# PL_IO.net
KiCad netlist of a schematic drawn in Altium Designer
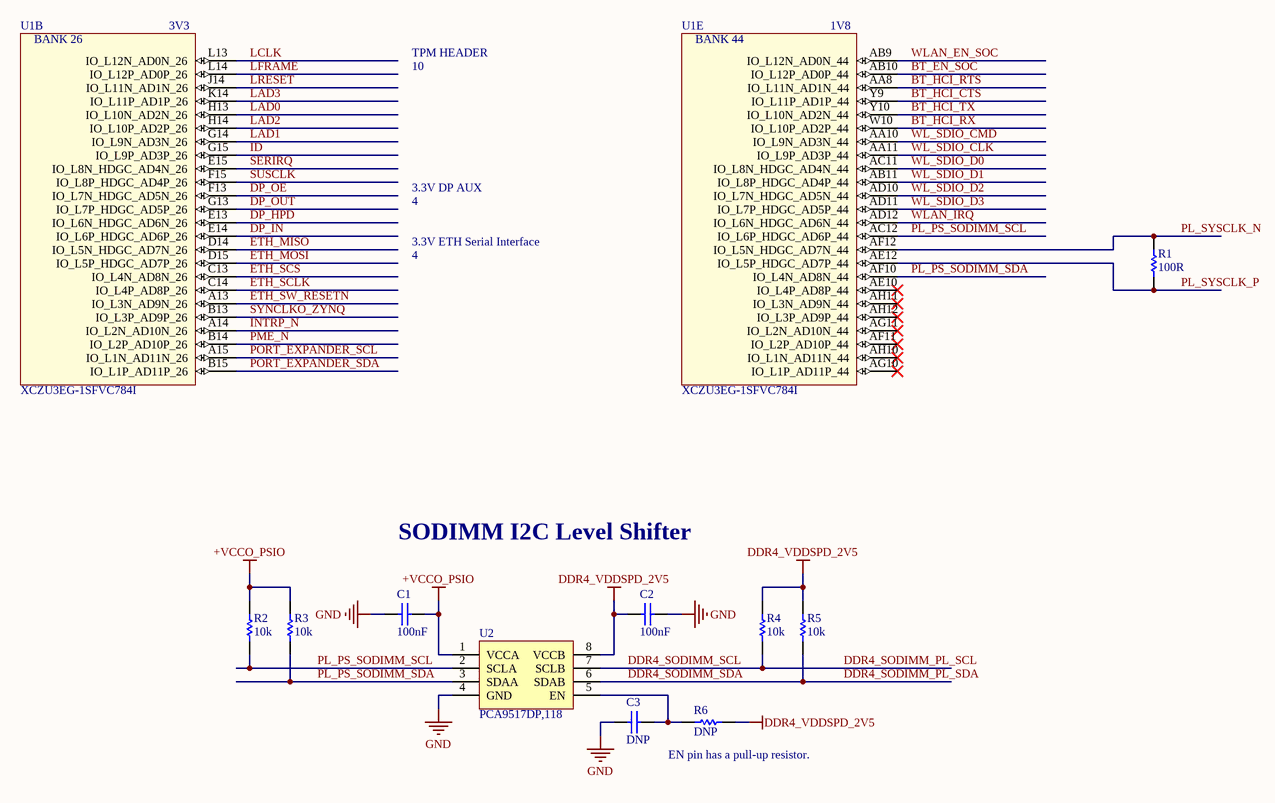
[diagram p0: PL_IO.SchDoc]

(export (version "E")
  (design (tool "Eeschema 10.0.6"))
  (components
    (comp (ref "C1")
      (value "100nF")
      (footprint "CAPC1005L_0402")
      (description "CAP CER 0.1UF 25V X7R 0402")
      (fields (field (name "VOLTAGE") "25V") (field (name "TOLERANCE") "10%"))
      (libsource (lib "Ultrascale_SchLib") (part "CAPCER0402X7R100N25V_10T"))
    )
    (comp (ref "C2")
      (value "100nF")
      (footprint "CAPC1005L_0402")
      (description "CAP CER 0.1UF 25V X7R 0402")
      (fields (field (name "VOLTAGE") "25V") (field (name "TOLERANCE") "10%"))
      (libsource (lib "Ultrascale_SchLib") (part "CAPCER0402X7R100N25V_10T"))
    )
    (comp (ref "C3")
      (value "DNP")
      (footprint "CAPC1005L_0402")
      (description "0402 Package Cap Footprint")
      (libsource (lib "Ultrascale_SchLib") (part "CAPCER0402"))
    )
    (comp (ref "R1")
      (value "100R")
      (footprint "RESC1005L_0402")
      (description "RES SMD 100 OHM 1% 1/10W 0402")
      (fields (field (name "POWER") "1/10W") (field (name "TOLERANCE") "1%"))
      (libsource (lib "Ultrascale_SchLib") (part "RES0402_100R_0W1_1T"))
    )
    (comp (ref "R2")
      (value "10k")
      (footprint "RESC1005L_0402")
      (description "RES SMD 10K OHM 0.5% 1/16W 0402")
      (fields (field (name "POWER") "1/16W") (field (name "TOLERANCE") "0.5%"))
      (libsource (lib "Ultrascale_SchLib") (part "RES0402_10K_0W1_05T"))
    )
    (comp (ref "R3")
      (value "10k")
      (footprint "RESC1005L_0402")
      (description "RES SMD 10K OHM 0.5% 1/16W 0402")
      (fields (field (name "POWER") "1/16W") (field (name "TOLERANCE") "0.5%"))
      (libsource (lib "Ultrascale_SchLib") (part "RES0402_10K_0W1_05T"))
    )
    (comp (ref "R4")
      (value "10k")
      (footprint "RESC1005L_0402")
      (description "RES SMD 10K OHM 0.5% 1/16W 0402")
      (fields (field (name "POWER") "1/16W") (field (name "TOLERANCE") "0.5%"))
      (libsource (lib "Ultrascale_SchLib") (part "RES0402_10K_0W1_05T"))
    )
    (comp (ref "R5")
      (value "10k")
      (footprint "RESC1005L_0402")
      (description "RES SMD 10K OHM 0.5% 1/16W 0402")
      (fields (field (name "POWER") "1/16W") (field (name "TOLERANCE") "0.5%"))
      (libsource (lib "Ultrascale_SchLib") (part "RES0402_10K_0W1_05T"))
    )
    (comp (ref "R6")
      (value "DNP")
      (footprint "RESC1005L_0402")
      (description "RES SMD 0402 Footprint")
      (fields (field (name "Comment") "RES0402"))
      (libsource (lib "Ultrascale_SchLib") (part "RES0402"))
    )
    (comp (ref "U1")
      (value "XCZU3EG-1SFVC784I")
      (footprint "BGA784x28")
      (description "IC FPGA 252 I/O 784FCBGA - XILINX ZYNQ ULTRASCALE+")
      (libsource (lib "Ultrascale_SchLib") (part "XCZU3EG-1SFVC784I"))
    )
    (comp (ref "U2")
      (value "PCA9517DP,118")
      (footprint "MSOP8_PCA9517DP,118")
      (description "IC REDRIVER I2C 1CH 8TSSOP")
      (libsource (lib "Ultrascale_SchLib") (part "PCA9517DP,118"))
    )
  )
  (nets
    (net (code "1") (name "+VCCO_PSIO") (class "Default")
      (node (ref "C1") (pin "2") (pinfunction "2_2") (pintype "passive"))
      (node (ref "R2") (pin "2") (pinfunction "2_2") (pintype "passive"))
      (node (ref "R3") (pin "2") (pinfunction "2_2") (pintype "passive"))
      (node (ref "U2") (pin "1") (pinfunction "VCCA_1") (pintype "passive"))
    )
    (net (code "2") (name "/BT_EN_SOC") (class "Default")
      (node (ref "U1") (pin "AB10") (pinfunction "IO_L12P_AD0P_44_AB10") (pintype "bidirectional"))
    )
    (net (code "3") (name "/BT_HCI_CTS") (class "Default")
      (node (ref "U1") (pin "Y9") (pinfunction "IO_L11P_AD1P_44_Y9") (pintype "bidirectional"))
    )
    (net (code "4") (name "/BT_HCI_RTS") (class "Default")
      (node (ref "U1") (pin "AA8") (pinfunction "IO_L11N_AD1N_44_AA8") (pintype "bidirectional"))
    )
    (net (code "5") (name "/BT_HCI_RX") (class "Default")
      (node (ref "U1") (pin "W10") (pinfunction "IO_L10P_AD2P_44_W10") (pintype "bidirectional"))
    )
    (net (code "6") (name "/BT_HCI_TX") (class "Default")
      (node (ref "U1") (pin "Y10") (pinfunction "IO_L10N_AD2N_44_Y10") (pintype "bidirectional"))
    )
    (net (code "7") (name "/DDR4_SODIMM_PL_SCL") (class "Default")
      (node (ref "R4") (pin "1") (pinfunction "1_1") (pintype "passive"))
      (node (ref "U2") (pin "7") (pinfunction "SCLB_7") (pintype "passive"))
    )
    (net (code "8") (name "/DDR4_SODIMM_PL_SDA") (class "Default")
      (node (ref "R5") (pin "1") (pinfunction "1_1") (pintype "passive"))
      (node (ref "U2") (pin "6") (pinfunction "SDAB_6") (pintype "passive"))
    )
    (net (code "9") (name "/DP_HPD") (class "Default")
      (node (ref "U1") (pin "E13") (pinfunction "IO_L6N_HDGC_AD6N_26_E13") (pintype "bidirectional"))
    )
    (net (code "10") (name "/DP_IN") (class "Default")
      (node (ref "U1") (pin "E14") (pinfunction "IO_L6P_HDGC_AD6P_26_E14") (pintype "bidirectional"))
    )
    (net (code "11") (name "/DP_OE") (class "Default")
      (node (ref "U1") (pin "F13") (pinfunction "IO_L7N_HDGC_AD5N_26_F13") (pintype "bidirectional"))
    )
    (net (code "12") (name "/DP_OUT") (class "Default")
      (node (ref "U1") (pin "G13") (pinfunction "IO_L7P_HDGC_AD5P_26_G13") (pintype "bidirectional"))
    )
    (net (code "13") (name "/ETH_MISO") (class "Default")
      (node (ref "U1") (pin "D14") (pinfunction "IO_L5N_HDGC_AD7N_26_D14") (pintype "bidirectional"))
    )
    (net (code "14") (name "/ETH_MOSI") (class "Default")
      (node (ref "U1") (pin "D15") (pinfunction "IO_L5P_HDGC_AD7P_26_D15") (pintype "bidirectional"))
    )
    (net (code "15") (name "/ETH_SCLK") (class "Default")
      (node (ref "U1") (pin "C14") (pinfunction "IO_L4P_AD8P_26_C14") (pintype "bidirectional"))
    )
    (net (code "16") (name "/ETH_SCS") (class "Default")
      (node (ref "U1") (pin "C13") (pinfunction "IO_L4N_AD8N_26_C13") (pintype "bidirectional"))
    )
    (net (code "17") (name "/ETH_SW_RESETN") (class "Default")
      (node (ref "U1") (pin "A13") (pinfunction "IO_L3N_AD9N_26_A13") (pintype "bidirectional"))
    )
    (net (code "18") (name "/ID") (class "Default")
      (node (ref "U1") (pin "G15") (pinfunction "IO_L9P_AD3P_26_G15") (pintype "bidirectional"))
    )
    (net (code "19") (name "/INTRP_N") (class "Default")
      (node (ref "U1") (pin "A14") (pinfunction "IO_L2N_AD10N_26_A14") (pintype "bidirectional"))
    )
    (net (code "20") (name "/LAD0") (class "Default")
      (node (ref "U1") (pin "H13") (pinfunction "IO_L10N_AD2N_26_H13") (pintype "bidirectional"))
    )
    (net (code "21") (name "/LAD1") (class "Default")
      (node (ref "U1") (pin "G14") (pinfunction "IO_L9N_AD3N_26_G14") (pintype "bidirectional"))
    )
    (net (code "22") (name "/LAD2") (class "Default")
      (node (ref "U1") (pin "H14") (pinfunction "IO_L10P_AD2P_26_H14") (pintype "bidirectional"))
    )
    (net (code "23") (name "/LAD3") (class "Default")
      (node (ref "U1") (pin "K14") (pinfunction "IO_L11P_AD1P_26_K14") (pintype "bidirectional"))
    )
    (net (code "24") (name "/LCLK") (class "Default")
      (node (ref "U1") (pin "L13") (pinfunction "IO_L12N_AD0N_26_L13") (pintype "bidirectional"))
    )
    (net (code "25") (name "/LFRAME") (class "Default")
      (node (ref "U1") (pin "L14") (pinfunction "IO_L12P_AD0P_26_L14") (pintype "bidirectional"))
    )
    (net (code "26") (name "/LRESET") (class "Default")
      (node (ref "U1") (pin "J14") (pinfunction "IO_L11N_AD1N_26_J14") (pintype "bidirectional"))
    )
    (net (code "27") (name "/PL_PS_SODIMM_SCL") (class "Default")
      (node (ref "R2") (pin "1") (pinfunction "1_1") (pintype "passive"))
      (node (ref "U1") (pin "AC12") (pinfunction "IO_L6P_HDGC_AD6P_44_AC12") (pintype "bidirectional"))
      (node (ref "U2") (pin "2") (pinfunction "SCLA_2") (pintype "passive"))
    )
    (net (code "28") (name "/PL_PS_SODIMM_SDA") (class "Default")
      (node (ref "R3") (pin "1") (pinfunction "1_1") (pintype "passive"))
      (node (ref "U1") (pin "AF10") (pinfunction "IO_L4N_AD8N_44_AF10") (pintype "bidirectional"))
      (node (ref "U2") (pin "3") (pinfunction "SDAA_3") (pintype "passive"))
    )
    (net (code "29") (name "/PL_SYSCLK_N") (class "Default")
      (node (ref "R1") (pin "2") (pinfunction "2_2") (pintype "passive"))
      (node (ref "U1") (pin "AF12") (pinfunction "IO_L5N_HDGC_AD7N_44_AF12") (pintype "bidirectional"))
    )
    (net (code "30") (name "/PL_SYSCLK_P") (class "Default")
      (node (ref "R1") (pin "1") (pinfunction "1_1") (pintype "passive"))
      (node (ref "U1") (pin "AE12") (pinfunction "IO_L5P_HDGC_AD7P_44_AE12") (pintype "bidirectional"))
    )
    (net (code "31") (name "/PME_N") (class "Default")
      (node (ref "U1") (pin "B14") (pinfunction "IO_L2P_AD10P_26_B14") (pintype "bidirectional"))
    )
    (net (code "32") (name "/PORT_EXPANDER_SCL") (class "Default")
      (node (ref "U1") (pin "A15") (pinfunction "IO_L1N_AD11N_26_A15") (pintype "bidirectional"))
    )
    (net (code "33") (name "/PORT_EXPANDER_SDA") (class "Default")
      (node (ref "U1") (pin "B15") (pinfunction "IO_L1P_AD11P_26_B15") (pintype "bidirectional"))
    )
    (net (code "34") (name "/SERIRQ") (class "Default")
      (node (ref "U1") (pin "E15") (pinfunction "IO_L8N_HDGC_AD4N_26_E15") (pintype "bidirectional"))
    )
    (net (code "35") (name "/SUSCLK") (class "Default")
      (node (ref "U1") (pin "F15") (pinfunction "IO_L8P_HDGC_AD4P_26_F15") (pintype "bidirectional"))
    )
    (net (code "36") (name "/SYNCLKO_ZYNQ") (class "Default")
      (node (ref "U1") (pin "B13") (pinfunction "IO_L3P_AD9P_26_B13") (pintype "bidirectional"))
    )
    (net (code "37") (name "/WLAN_EN_SOC") (class "Default")
      (node (ref "U1") (pin "AB9") (pinfunction "IO_L12N_AD0N_44_AB9") (pintype "bidirectional"))
    )
    (net (code "38") (name "/WLAN_IRQ") (class "Default")
      (node (ref "U1") (pin "AD12") (pinfunction "IO_L6N_HDGC_AD6N_44_AD12") (pintype "bidirectional"))
    )
    (net (code "39") (name "/WL_SDIO_CLK") (class "Default")
      (node (ref "U1") (pin "AA11") (pinfunction "IO_L9P_AD3P_44_AA11") (pintype "bidirectional"))
    )
    (net (code "40") (name "/WL_SDIO_CMD") (class "Default")
      (node (ref "U1") (pin "AA10") (pinfunction "IO_L9N_AD3N_44_AA10") (pintype "bidirectional"))
    )
    (net (code "41") (name "/WL_SDIO_D0") (class "Default")
      (node (ref "U1") (pin "AC11") (pinfunction "IO_L8N_HDGC_AD4N_44_AC11") (pintype "bidirectional"))
    )
    (net (code "42") (name "/WL_SDIO_D1") (class "Default")
      (node (ref "U1") (pin "AB11") (pinfunction "IO_L8P_HDGC_AD4P_44_AB11") (pintype "bidirectional"))
    )
    (net (code "43") (name "/WL_SDIO_D2") (class "Default")
      (node (ref "U1") (pin "AD10") (pinfunction "IO_L7N_HDGC_AD5N_44_AD10") (pintype "bidirectional"))
    )
    (net (code "44") (name "/WL_SDIO_D3") (class "Default")
      (node (ref "U1") (pin "AD11") (pinfunction "IO_L7P_HDGC_AD5P_44_AD11") (pintype "bidirectional"))
    )
    (net (code "45") (name "DDR4_VDDSPD_2V5") (class "Default")
      (node (ref "C2") (pin "1") (pinfunction "1_1") (pintype "passive"))
      (node (ref "R4") (pin "2") (pinfunction "2_2") (pintype "passive"))
      (node (ref "R5") (pin "2") (pinfunction "2_2") (pintype "passive"))
      (node (ref "R6") (pin "2") (pinfunction "2_2") (pintype "passive"))
      (node (ref "U2") (pin "8") (pinfunction "VCCB_8") (pintype "passive"))
    )
    (net (code "46") (name "GND") (class "Default")
      (node (ref "C1") (pin "1") (pinfunction "1_1") (pintype "passive"))
      (node (ref "C2") (pin "2") (pinfunction "2_2") (pintype "passive"))
      (node (ref "C3") (pin "1") (pinfunction "1_1") (pintype "passive"))
      (node (ref "U2") (pin "4") (pinfunction "GND_4") (pintype "passive"))
    )
    (net (code "47") (name "Net-(U2-EN)") (class "Default")
      (node (ref "C3") (pin "2") (pinfunction "2_2") (pintype "passive"))
      (node (ref "R6") (pin "1") (pinfunction "1_1") (pintype "passive"))
      (node (ref "U2") (pin "5") (pinfunction "EN_5") (pintype "passive"))
    )
    (net (code "48") (name "unconnected-(U1E-IO_L1N_AD11N_44-PadAH10)") (class "Default")
      (node (ref "U1") (pin "AH10") (pinfunction "IO_L1N_AD11N_44_AH10") (pintype "bidirectional+no_connect"))
    )
    (net (code "49") (name "unconnected-(U1E-IO_L1P_AD11P_44-PadAG10)") (class "Default")
      (node (ref "U1") (pin "AG10") (pinfunction "IO_L1P_AD11P_44_AG10") (pintype "bidirectional+no_connect"))
    )
    (net (code "50") (name "unconnected-(U1E-IO_L2N_AD10N_44-PadAG11)") (class "Default")
      (node (ref "U1") (pin "AG11") (pinfunction "IO_L2N_AD10N_44_AG11") (pintype "bidirectional+no_connect"))
    )
    (net (code "51") (name "unconnected-(U1E-IO_L2P_AD10P_44-PadAF11)") (class "Default")
      (node (ref "U1") (pin "AF11") (pinfunction "IO_L2P_AD10P_44_AF11") (pintype "bidirectional+no_connect"))
    )
    (net (code "52") (name "unconnected-(U1E-IO_L3N_AD9N_44-PadAH11)") (class "Default")
      (node (ref "U1") (pin "AH11") (pinfunction "IO_L3N_AD9N_44_AH11") (pintype "bidirectional+no_connect"))
    )
    (net (code "53") (name "unconnected-(U1E-IO_L3P_AD9P_44-PadAH12)") (class "Default")
      (node (ref "U1") (pin "AH12") (pinfunction "IO_L3P_AD9P_44_AH12") (pintype "bidirectional+no_connect"))
    )
    (net (code "54") (name "unconnected-(U1E-IO_L4P_AD8P_44-PadAE10)") (class "Default")
      (node (ref "U1") (pin "AE10") (pinfunction "IO_L4P_AD8P_44_AE10") (pintype "bidirectional+no_connect"))
    )
  )
)
